# Power_Supply_Design.net
KiCad netlist of a schematic drawn in EAGLE
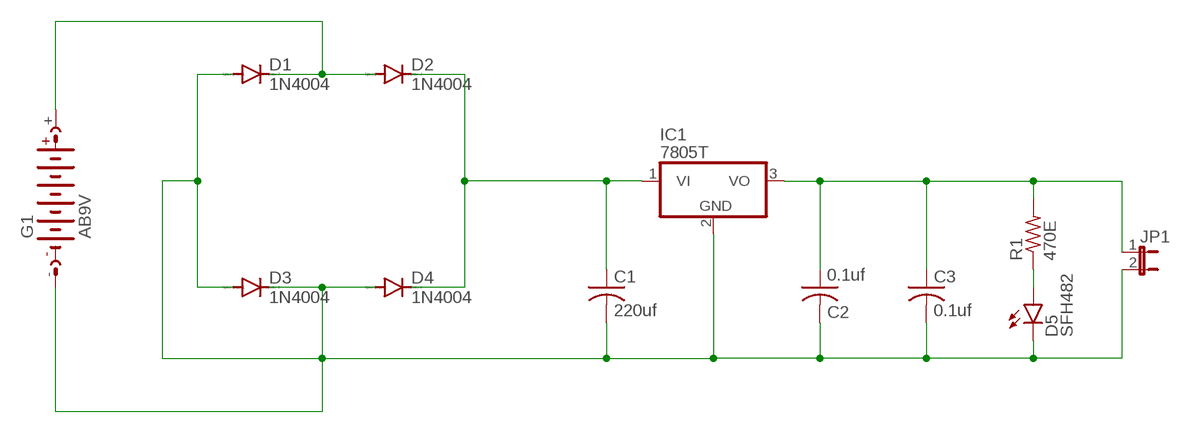
[diagram p0: schematic, sheet 1]

(export (version "E")
  (design (tool "Eeschema 10.0.6"))
  (components
    (comp (ref "C1")
      (value "220uf")
      (footprint "eagle-import:C050-030X075")
      (libsource (lib "eagle-import") (part "C-US050-030X075"))
    )
    (comp (ref "C2")
      (value "0.1uf")
      (footprint "eagle-import:C050-030X075")
      (libsource (lib "eagle-import") (part "C-US050-030X075"))
    )
    (comp (ref "C3")
      (value "0.1uf")
      (footprint "eagle-import:C050-030X075")
      (libsource (lib "eagle-import") (part "C-US050-030X075"))
    )
    (comp (ref "D1")
      (value "1N4004")
      (footprint "eagle-import:DO41-10")
      (libsource (lib "eagle-import") (part "1N4004"))
    )
    (comp (ref "D2")
      (value "1N4004")
      (footprint "eagle-import:DO41-10")
      (libsource (lib "eagle-import") (part "1N4004"))
    )
    (comp (ref "D3")
      (value "1N4004")
      (footprint "eagle-import:DO41-10")
      (libsource (lib "eagle-import") (part "1N4004"))
    )
    (comp (ref "D4")
      (value "1N4004")
      (footprint "eagle-import:DO41-10")
      (libsource (lib "eagle-import") (part "1N4004"))
    )
    (comp (ref "D5")
      (value "SFH482")
      (footprint "eagle-import:SFH482")
      (libsource (lib "eagle-import") (part "SFH482"))
    )
    (comp (ref "G1")
      (value "AB9V")
      (footprint "eagle-import:AB9V")
      (libsource (lib "eagle-import") (part "AB9V"))
    )
    (comp (ref "IC1")
      (value "7805T")
      (footprint "eagle-import:TO220H")
      (libsource (lib "eagle-import") (part "78T05"))
    )
    (comp (ref "JP1")
      (value "JP1E")
      (footprint "eagle-import:JP1")
      (libsource (lib "eagle-import") (part "JP1E"))
    )
    (comp (ref "R1")
      (value "470E")
      (footprint "eagle-import:0204_7")
      (libsource (lib "eagle-import") (part "R-US_0204/7"))
    )
  )
  (nets
    (net (code "1") (name "Net-(D1-PadC)") (class "Default")
      (node (ref "D1") (pin "C") (pinfunction "C_C") (pintype "passive"))
      (node (ref "D2") (pin "A") (pinfunction "A_A") (pintype "passive"))
      (node (ref "G1") (pin "+") (pinfunction "+_+") (pintype "passive"))
    )
    (net (code "2") (name "Net-(D5-C)") (class "Default")
      (node (ref "C1") (pin "2") (pinfunction "2_2") (pintype "passive"))
      (node (ref "C2") (pin "2") (pinfunction "2_2") (pintype "passive"))
      (node (ref "C3") (pin "2") (pinfunction "2_2") (pintype "passive"))
      (node (ref "D1") (pin "A") (pinfunction "A_A") (pintype "passive"))
      (node (ref "D3") (pin "A") (pinfunction "A_A") (pintype "passive"))
      (node (ref "D3") (pin "C") (pinfunction "C_C") (pintype "passive"))
      (node (ref "D4") (pin "A") (pinfunction "A_A") (pintype "passive"))
      (node (ref "D5") (pin "K") (pinfunction "C_K") (pintype "passive"))
      (node (ref "G1") (pin "-") (pinfunction "-_-") (pintype "passive"))
      (node (ref "IC1") (pin "2") (pinfunction "GND_2") (pintype "passive"))
      (node (ref "JP1") (pin "2") (pinfunction "2_2") (pintype "passive"))
    )
    (net (code "3") (name "Net-(D5-PadA)") (class "Default")
      (node (ref "D5") (pin "A") (pinfunction "A_A") (pintype "passive"))
      (node (ref "R1") (pin "1") (pinfunction "1_1") (pintype "passive"))
    )
    (net (code "4") (name "Net-(IC1-VI)") (class "Default")
      (node (ref "C1") (pin "1") (pinfunction "1_1") (pintype "passive"))
      (node (ref "D2") (pin "C") (pinfunction "C_C") (pintype "passive"))
      (node (ref "D4") (pin "C") (pinfunction "C_C") (pintype "passive"))
      (node (ref "IC1") (pin "1") (pinfunction "VI_1") (pintype "input"))
    )
    (net (code "5") (name "Net-(IC1-VO)") (class "Default")
      (node (ref "C2") (pin "1") (pinfunction "1_1") (pintype "passive"))
      (node (ref "C3") (pin "1") (pinfunction "1_1") (pintype "passive"))
      (node (ref "IC1") (pin "3") (pinfunction "VO_3") (pintype "passive"))
      (node (ref "JP1") (pin "1") (pinfunction "1_1") (pintype "passive"))
      (node (ref "R1") (pin "2") (pinfunction "2_2") (pintype "passive"))
    )
  )
)
